# ADCS_C2Sv0_1_-_Shield_TopLevel.net
KiCad netlist of a schematic drawn in Altium Designer
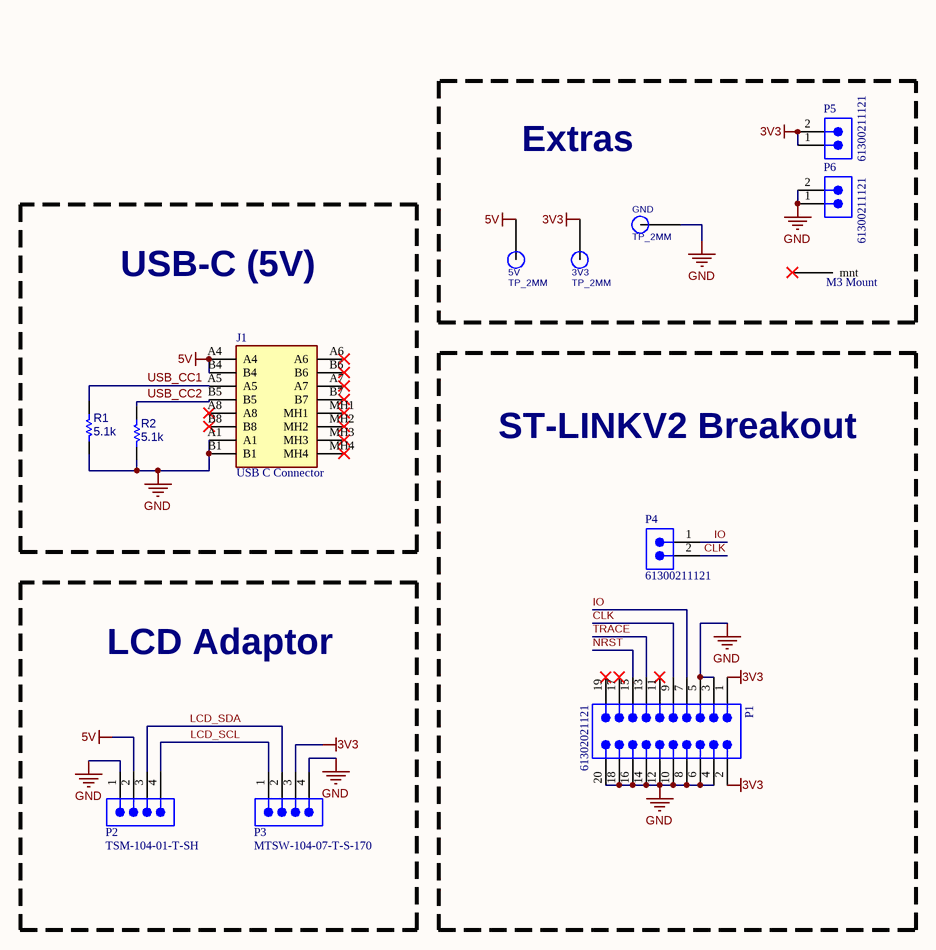
[diagram p0: ADCS C2Sv0.1 - Shield_TopLevel.SchDoc]

(export (version "E")
  (design (tool "Eeschema 10.0.6"))
  (components
    (comp (ref "3V3") (value "TP_2MM") (footprint "TESTPOINT 2MM") (libsource (lib "C2S") (part "TP_2MM")))
    (comp (ref "5V") (value "TP_2MM") (footprint "TESTPOINT 2MM") (libsource (lib "C2S") (part "TP_2MM")))
    (comp (ref "GND") (value "TP_2MM") (footprint "TESTPOINT 2MM") (libsource (lib "C2S") (part "TP_2MM")))
    (comp (ref "J1")
      (value "USB C Connector")
      (footprint "UJ20CHGMSMT2P16TR")
      (description "UJ20-C-H-G-MSMT-2-P16-TR Connector")
      (fields
        (field (name "MOUSER PART NUMBER") "179-UJ20CHGMSMT2P16T")
        (field (name "MANUFACTURER_PART_NUMBER") "UJ20-C-H-G-MSMT-2-P16-TR")
        (field (name "AUTHOR") "Raphael Ho")
      )
      (libsource (lib "Perth Aerospace Student Team") (part "UJ20-C-H-G-MSMT-2-P16-TR"))
    )
    (comp (ref "MNT1")
      (value "M3 Mount")
      (footprint "M3_Mount-Footprint-1")
      (description "M3 mounting hole")
      (fields (field (name "AUTHOR") "Raphael Ho"))
      (libsource (lib "Perth Aerospace Student Team") (part "M3_Mount-Symbol-1"))
    )
    (comp (ref "P1")
      (value "61302021121")
      (footprint "61302021121")
      (description "THT Vertical Pin Header WR-PHD, Pitch 2.54 mm, Dual Row, 20 pins")
      (libsource (lib "Altium Content Vault") (part "Header_Male_2R_20P"))
    )
    (comp (ref "P2")
      (value "TSM-104-01-T-SH")
      (footprint "SMTC-TSM-104-01-X-SH")
      (fields (field (name "MANUFACTURER") "Samtec"))
      (libsource (lib "Altium Content Vault") (part "SMTC-TSM-104-01-X-SH"))
    )
    (comp (ref "P3")
      (value "MTSW-104-07-T-S-170")
      (footprint "SMTC-MTSW-104-07-X-S-170")
      (fields (field (name "MANUFACTURER") "Samtec"))
      (libsource (lib "Altium Content Vault") (part "SMTC-MTSW-104-07-X-S-170"))
    )
    (comp (ref "P4")
      (value "61300211121")
      (footprint "61300211121")
      (description "WR-PHD Pin Header, THT, Vertical, pitch 2.54mm, 1 Row, 2P")
      (fields (field (name "MANUFACTURER") "Wurth Elektronik"))
      (libsource (lib "Perth Aerospace Student Team") (part "62000211121"))
    )
    (comp (ref "P5")
      (value "61300211121")
      (footprint "61300211121")
      (description "WR-PHD Pin Header, THT, Vertical, pitch 2.54mm, 1 Row, 2P")
      (fields (field (name "MANUFACTURER") "Wurth Elektronik"))
      (libsource (lib "Perth Aerospace Student Team") (part "62000211121"))
    )
    (comp (ref "P6")
      (value "61300211121")
      (footprint "61300211121")
      (description "WR-PHD Pin Header, THT, Vertical, pitch 2.54mm, 1 Row, 2P")
      (fields (field (name "MANUFACTURER") "Wurth Elektronik"))
      (libsource (lib "Perth Aerospace Student Team") (part "62000211121"))
    )
    (comp (ref "R1")
      (value "5.1k")
      (footprint "RESC1608X55X25ML10T15-1")
      (description "Chip Resistor, 10k Ohm, 0.1 W, -55 to 155 degC, 0603 (1608 Metric)")
      (fields
        (field (name "POWER") "100mW")
        (field (name "TOLERANCE") "1%")
        (field (name "CREATED BY") "Micah Randall")
      )
      (libsource (lib "Perth Aerospace Student Team") (part "CMP-009-00006-5"))
    )
    (comp (ref "R2")
      (value "5.1k")
      (footprint "RESC1608X55X25ML10T15-1")
      (description "Chip Resistor, 10k Ohm, 0.1 W, -55 to 155 degC, 0603 (1608 Metric)")
      (fields
        (field (name "POWER") "100mW")
        (field (name "TOLERANCE") "1%")
        (field (name "CREATED BY") "Micah Randall")
      )
      (libsource (lib "Perth Aerospace Student Team") (part "CMP-009-00006-5"))
    )
  )
  (nets
    (net (code "1") (name "/CLK") (class "Default")
      (node (ref "P1") (pin "9") (pinfunction "9_9") (pintype "passive"))
      (node (ref "P4") (pin "2") (pinfunction "2_2") (pintype "passive"))
    )
    (net (code "2") (name "/IO") (class "Default")
      (node (ref "P1") (pin "7") (pinfunction "7_7") (pintype "passive"))
      (node (ref "P4") (pin "1") (pinfunction "1_1") (pintype "passive"))
    )
    (net (code "3") (name "/LCD_SCL") (class "Default")
      (node (ref "P2") (pin "4") (pinfunction "4_4") (pintype "passive"))
      (node (ref "P3") (pin "1") (pinfunction "1_1") (pintype "passive"))
    )
    (net (code "4") (name "/LCD_SDA") (class "Default")
      (node (ref "P2") (pin "3") (pinfunction "3_3") (pintype "passive"))
      (node (ref "P3") (pin "2") (pinfunction "2_2") (pintype "passive"))
    )
    (net (code "5") (name "/NRST") (class "Default")
      (node (ref "P1") (pin "15") (pinfunction "15_15") (pintype "passive"))
    )
    (net (code "6") (name "/TRACE") (class "Default")
      (node (ref "P1") (pin "13") (pinfunction "13_13") (pintype "passive"))
    )
    (net (code "7") (name "/USB_CC1") (class "Default")
      (node (ref "J1") (pin "A5") (pinfunction "A5_A5") (pintype "passive"))
      (node (ref "R1") (pin "1") (pinfunction "1_1") (pintype "passive"))
    )
    (net (code "8") (name "/USB_CC2") (class "Default")
      (node (ref "J1") (pin "B5") (pinfunction "B5_B5") (pintype "passive"))
      (node (ref "R2") (pin "1") (pinfunction "1_1") (pintype "passive"))
    )
    (net (code "9") (name "3V3") (class "Default")
      (node (ref "3V3") (pin "TP") (pinfunction "TP_2MM_TP") (pintype "passive"))
      (node (ref "P1") (pin "1") (pinfunction "1_1") (pintype "passive"))
      (node (ref "P1") (pin "2") (pinfunction "2_2") (pintype "passive"))
      (node (ref "P3") (pin "3") (pinfunction "3_3") (pintype "passive"))
      (node (ref "P5") (pin "1") (pinfunction "1_1") (pintype "passive"))
      (node (ref "P5") (pin "2") (pinfunction "2_2") (pintype "passive"))
    )
    (net (code "10") (name "5V") (class "Default")
      (node (ref "5V") (pin "TP") (pinfunction "TP_2MM_TP") (pintype "passive"))
      (node (ref "J1") (pin "A4") (pinfunction "A4_A4") (pintype "passive"))
      (node (ref "J1") (pin "B4") (pinfunction "B4_B4") (pintype "passive"))
      (node (ref "P2") (pin "2") (pinfunction "2_2") (pintype "passive"))
    )
    (net (code "11") (name "GND") (class "Default")
      (node (ref "GND") (pin "TP") (pinfunction "TP_2MM_TP") (pintype "passive"))
      (node (ref "J1") (pin "A1") (pinfunction "A1_A1") (pintype "passive"))
      (node (ref "J1") (pin "B1") (pinfunction "B1_B1") (pintype "passive"))
      (node (ref "P1") (pin "10") (pinfunction "10_10") (pintype "passive"))
      (node (ref "P1") (pin "12") (pinfunction "12_12") (pintype "passive"))
      (node (ref "P1") (pin "14") (pinfunction "14_14") (pintype "passive"))
      (node (ref "P1") (pin "16") (pinfunction "16_16") (pintype "passive"))
      (node (ref "P1") (pin "18") (pinfunction "18_18") (pintype "passive"))
      (node (ref "P1") (pin "20") (pinfunction "20_20") (pintype "passive"))
      (node (ref "P1") (pin "3") (pinfunction "3_3") (pintype "passive"))
      (node (ref "P1") (pin "4") (pinfunction "4_4") (pintype "passive"))
      (node (ref "P1") (pin "5") (pinfunction "5_5") (pintype "passive"))
      (node (ref "P1") (pin "6") (pinfunction "6_6") (pintype "passive"))
      (node (ref "P1") (pin "8") (pinfunction "8_8") (pintype "passive"))
      (node (ref "P2") (pin "1") (pinfunction "1_1") (pintype "passive"))
      (node (ref "P3") (pin "4") (pinfunction "4_4") (pintype "passive"))
      (node (ref "P6") (pin "1") (pinfunction "1_1") (pintype "passive"))
      (node (ref "P6") (pin "2") (pinfunction "2_2") (pintype "passive"))
      (node (ref "R1") (pin "2") (pinfunction "2_2") (pintype "passive"))
      (node (ref "R2") (pin "2") (pinfunction "2_2") (pintype "passive"))
    )
    (net (code "12") (name "unconnected-(J1-PadA6)") (class "Default")
      (node (ref "J1") (pin "A6") (pinfunction "A6_A6") (pintype "passive+no_connect"))
    )
    (net (code "13") (name "unconnected-(J1-PadA7)") (class "Default")
      (node (ref "J1") (pin "A7") (pinfunction "A7_A7") (pintype "passive+no_connect"))
    )
    (net (code "14") (name "unconnected-(J1-PadA8)") (class "Default")
      (node (ref "J1") (pin "A8") (pinfunction "A8_A8") (pintype "passive+no_connect"))
    )
    (net (code "15") (name "unconnected-(J1-PadB6)") (class "Default")
      (node (ref "J1") (pin "B6") (pinfunction "B6_B6") (pintype "passive+no_connect"))
    )
    (net (code "16") (name "unconnected-(J1-PadB7)") (class "Default")
      (node (ref "J1") (pin "B7") (pinfunction "B7_B7") (pintype "passive+no_connect"))
    )
    (net (code "17") (name "unconnected-(J1-PadB8)") (class "Default")
      (node (ref "J1") (pin "B8") (pinfunction "B8_B8") (pintype "passive+no_connect"))
    )
    (net (code "18") (name "unconnected-(J1-PadMH1)") (class "Default")
      (node (ref "J1") (pin "MH1") (pinfunction "MH1_MH1") (pintype "passive+no_connect"))
    )
    (net (code "19") (name "unconnected-(J1-PadMH2)") (class "Default")
      (node (ref "J1") (pin "MH2") (pinfunction "MH2_MH2") (pintype "passive+no_connect"))
    )
    (net (code "20") (name "unconnected-(J1-PadMH3)") (class "Default")
      (node (ref "J1") (pin "MH3") (pinfunction "MH3_MH3") (pintype "passive+no_connect"))
    )
    (net (code "21") (name "unconnected-(J1-PadMH4)") (class "Default")
      (node (ref "J1") (pin "MH4") (pinfunction "MH4_MH4") (pintype "passive+no_connect"))
    )
    (net (code "22") (name "unconnected-(MNT1-mnt-Pad1)") (class "Default")
      (node (ref "MNT1") (pin "1") (pinfunction "mnt_1") (pintype "passive+no_connect"))
    )
    (net (code "23") (name "unconnected-(P1-Pad11)") (class "Default")
      (node (ref "P1") (pin "11") (pinfunction "11_11") (pintype "passive+no_connect"))
    )
    (net (code "24") (name "unconnected-(P1-Pad17)") (class "Default")
      (node (ref "P1") (pin "17") (pinfunction "17_17") (pintype "passive+no_connect"))
    )
    (net (code "25") (name "unconnected-(P1-Pad19)") (class "Default")
      (node (ref "P1") (pin "19") (pinfunction "19_19") (pintype "passive+no_connect"))
    )
  )
)
